# 1_ESP32-S3.net
KiCad netlist of a schematic drawn in Altium Designer
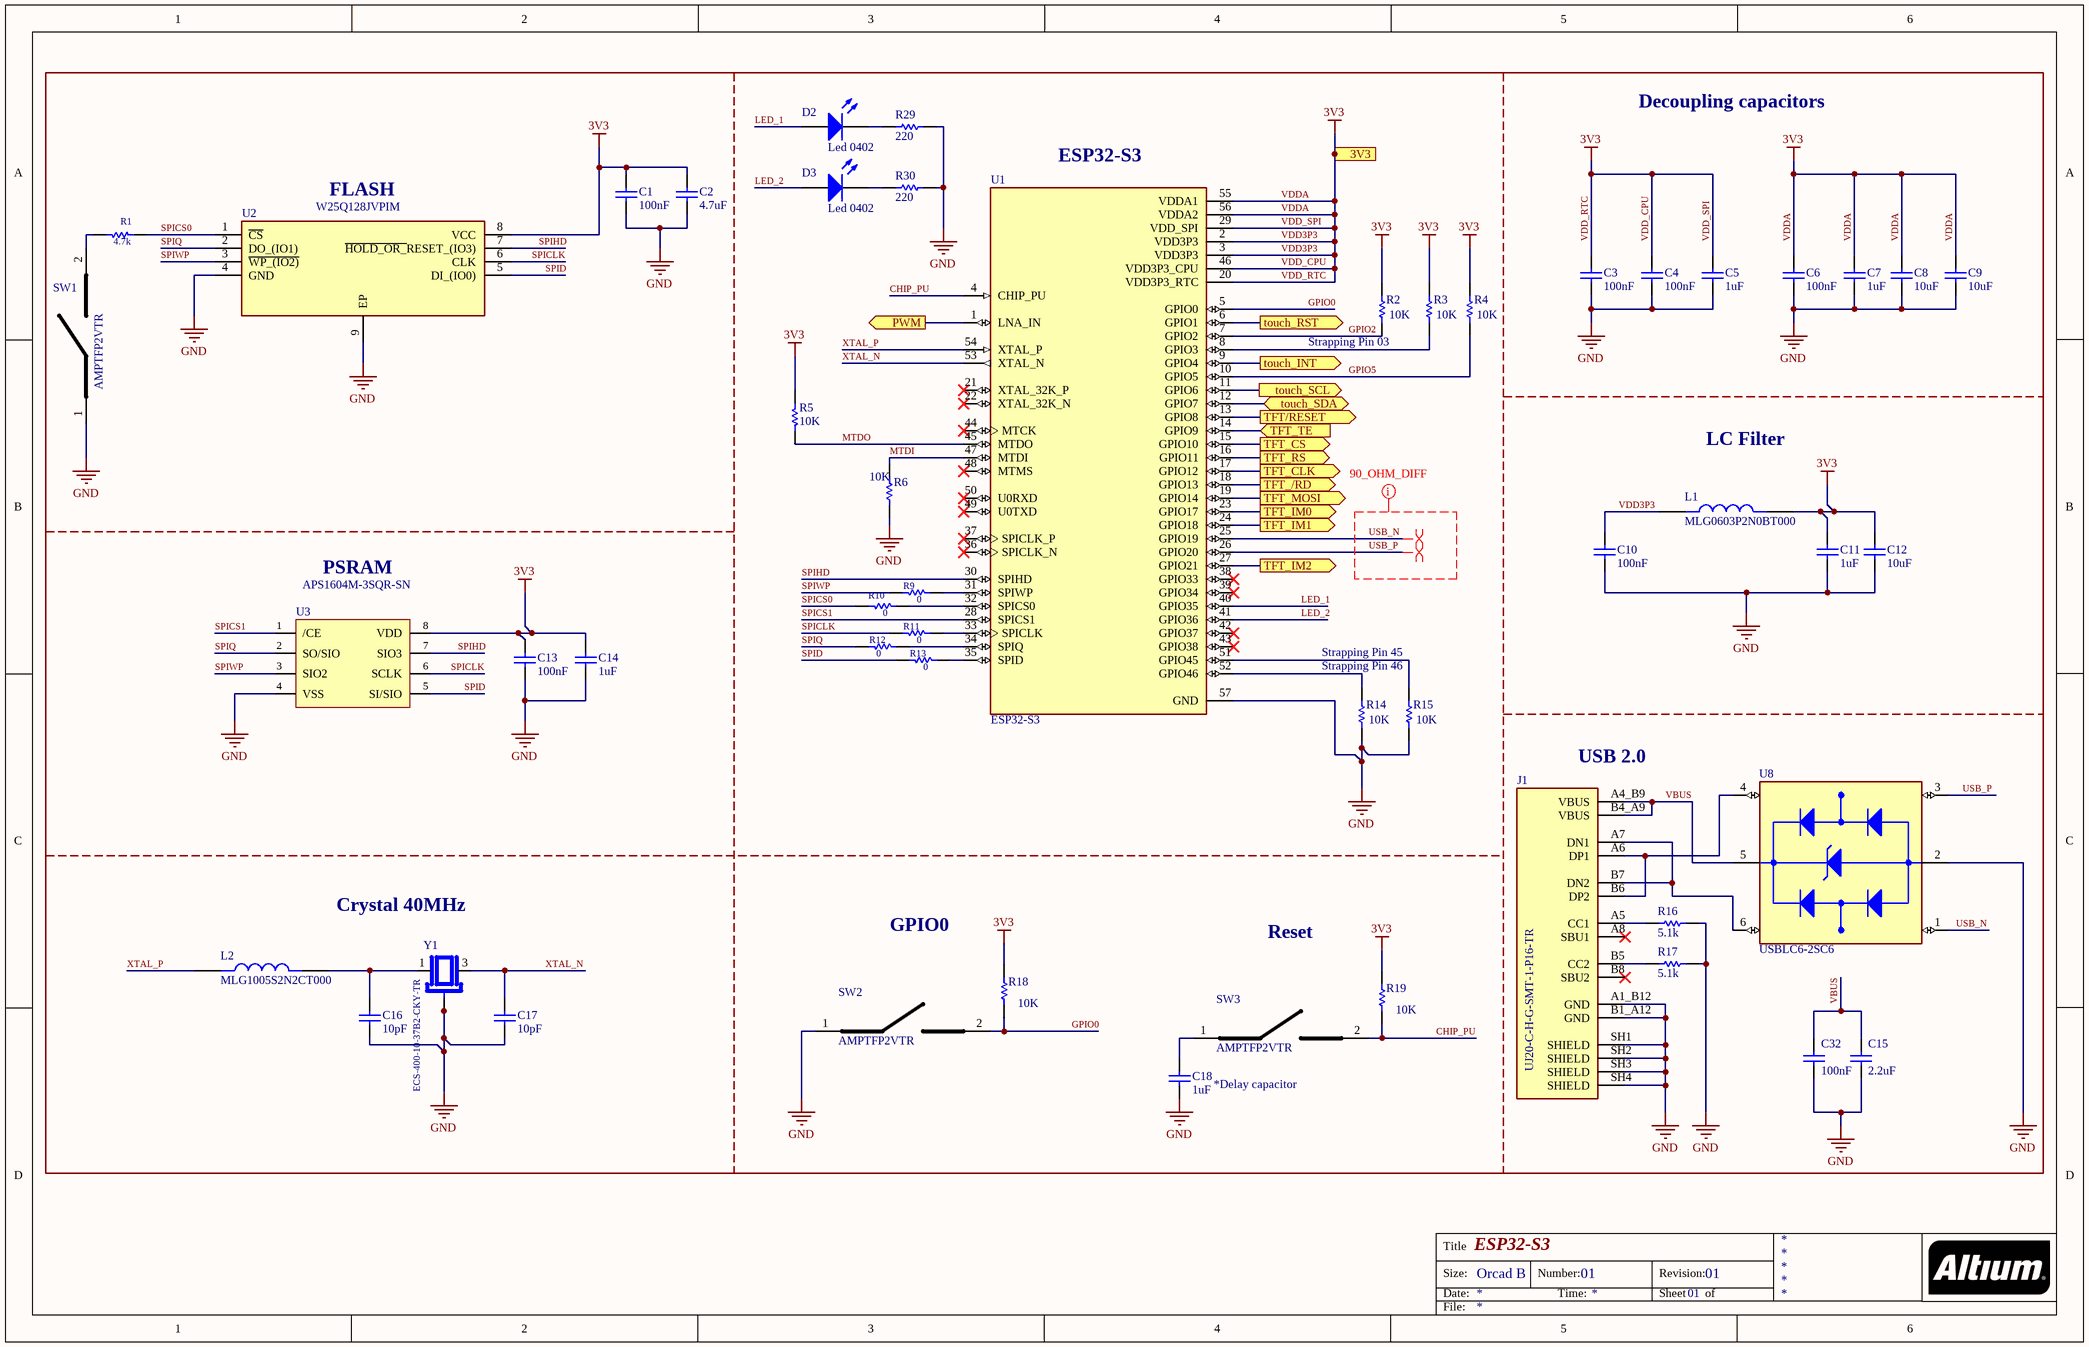
[diagram p0: [1] ESP32-S3.SchDoc]

(export (version "E")
  (design (tool "Eeschema 10.0.6"))
  (components
    (comp (ref "C1")
      (value "100nF")
      (footprint "Capacitor 0402")
      (description "Capacitor Ceramico SMD 0402")
      (libsource (lib "Mi Libreria") (part "Capacitor 0402"))
    )
    (comp (ref "C2")
      (value "4.7uF")
      (footprint "Capacitor 0402")
      (description "Capacitor Ceramico SMD 0402")
      (libsource (lib "Mi Libreria") (part "Capacitor 0402"))
    )
    (comp (ref "C3")
      (value "100nF")
      (footprint "Capacitor 0402")
      (description "Capacitor Ceramico SMD 0402")
      (libsource (lib "Mi Libreria") (part "Capacitor 0402"))
    )
    (comp (ref "C4")
      (value "100nF")
      (footprint "Capacitor 0402")
      (description "Capacitor Ceramico SMD 0402")
      (libsource (lib "Mi Libreria") (part "Capacitor 0402"))
    )
    (comp (ref "C5")
      (value "1uF")
      (footprint "Capacitor 0402")
      (description "Capacitor Ceramico SMD 0402")
      (libsource (lib "Mi Libreria") (part "Capacitor 0402"))
    )
    (comp (ref "C6")
      (value "100nF")
      (footprint "Capacitor 0402")
      (description "Capacitor Ceramico SMD 0402")
      (libsource (lib "Mi Libreria") (part "Capacitor 0402"))
    )
    (comp (ref "C7")
      (value "1uF")
      (footprint "Capacitor 0402")
      (description "Capacitor Ceramico SMD 0402")
      (libsource (lib "Mi Libreria") (part "Capacitor 0402"))
    )
    (comp (ref "C8")
      (value "10uF")
      (footprint "Capacitor 0603")
      (description "Capacitor Ceramico SMD 0603")
      (libsource (lib "Mi Libreria") (part "Capacitor 0603"))
    )
    (comp (ref "C9")
      (value "10uF")
      (footprint "Capacitor 0603")
      (description "Capacitor Ceramico SMD 0603")
      (libsource (lib "Mi Libreria") (part "Capacitor 0603"))
    )
    (comp (ref "C10")
      (value "100nF")
      (footprint "Capacitor 0402")
      (description "Capacitor Ceramico SMD 0402")
      (libsource (lib "Mi Libreria") (part "Capacitor 0402"))
    )
    (comp (ref "C11")
      (value "1uF")
      (footprint "Capacitor 0402")
      (description "Capacitor Ceramico SMD 0402")
      (libsource (lib "Mi Libreria") (part "Capacitor 0402"))
    )
    (comp (ref "C12")
      (value "10uF")
      (footprint "Capacitor 0603")
      (description "Capacitor Ceramico SMD 0603")
      (libsource (lib "Mi Libreria") (part "Capacitor 0603"))
    )
    (comp (ref "C13")
      (value "100nF")
      (footprint "Capacitor 0402")
      (description "Capacitor Ceramico SMD 0402")
      (libsource (lib "Mi Libreria") (part "Capacitor 0402"))
    )
    (comp (ref "C14")
      (value "1uF")
      (footprint "Capacitor 0402")
      (description "Capacitor Ceramico SMD 0402")
      (libsource (lib "Mi Libreria") (part "Capacitor 0402"))
    )
    (comp (ref "C15")
      (value "2.2uF")
      (footprint "Capacitor 0402")
      (description "Capacitor Ceramico SMD 0402")
      (libsource (lib "Mi Libreria") (part "Capacitor 0402"))
    )
    (comp (ref "C16")
      (value "10pF")
      (footprint "Capacitor 0402")
      (description "Capacitor Ceramico SMD 0402")
      (libsource (lib "Mi Libreria") (part "Capacitor 0402"))
    )
    (comp (ref "C17")
      (value "10pF")
      (footprint "Capacitor 0402")
      (description "Capacitor Ceramico SMD 0402")
      (libsource (lib "Mi Libreria") (part "Capacitor 0402"))
    )
    (comp (ref "C18")
      (value "1uF")
      (footprint "Capacitor 0402")
      (description "Capacitor Ceramico SMD 0402")
      (libsource (lib "Mi Libreria") (part "Capacitor 0402"))
    )
    (comp (ref "C32")
      (value "100nF")
      (footprint "Capacitor 0402")
      (description "Capacitor Ceramico SMD 0402")
      (libsource (lib "Mi Libreria") (part "Capacitor 0402"))
    )
    (comp (ref "D2")
      (value "Led 0402")
      (footprint "LED 0402")
      (description "LED SMD 0402")
      (libsource (lib "Led & Displays") (part "LED 0402"))
    )
    (comp (ref "D3")
      (value "Led 0402")
      (footprint "LED 0402")
      (description "LED SMD 0402")
      (libsource (lib "Led & Displays") (part "LED 0402"))
    )
    (comp (ref "J1")
      (value "UJ20-C-H-G-SMT-1-P16-TR")
      (footprint "SAMESKY_UJ20-C-H-G-SMT-1-P16-TR")
      (fields (field (name "MF") "Same Sky"))
      (libsource (lib "UJ20-C-H-G-SMT-1-P16-TR") (part "UJ20-C-H-G-SMT-1-P16-TR"))
    )
    (comp (ref "L1")
      (value "MLG0603P2N0BT000")
      (footprint "INDC0603X33N")
      (description "2 nH Unshielded Multilayer Inductor 600 mA 100mOhm Max 0201 (0603 Metric)")
      (fields (field (name "MF") "TDK"))
      (libsource (lib "MLG0603P2N0BT000") (part "MLG0603P2N0BT000"))
    )
    (comp (ref "L2")
      (value "MLG1005S2N2CT000")
      (footprint "INDC1005X55N")
      (description "FIXED IND 2.2NH 900MA 150MOHM SM")
      (fields (field (name "MF") "TDK Corporation"))
      (libsource (lib "0402inductor") (part "MLG1005S2N2CT000"))
    )
    (comp (ref "R1")
      (value "4.7k")
      (footprint "Resistencia 0402")
      (description "Resistencia SMD 0402")
      (libsource (lib "Mi Libreria") (part "Resistencia SMD 0402"))
    )
    (comp (ref "R2")
      (value "10K")
      (footprint "Resistencia 0402")
      (description "Resistencia SMD 0402")
      (libsource (lib "Mi Libreria") (part "Resistencia SMD 0402"))
    )
    (comp (ref "R3")
      (value "10K")
      (footprint "Resistencia 0402")
      (description "Resistencia SMD 0402")
      (libsource (lib "Mi Libreria") (part "Resistencia SMD 0402"))
    )
    (comp (ref "R4")
      (value "10K")
      (footprint "Resistencia 0402")
      (description "Resistencia SMD 0402")
      (libsource (lib "Mi Libreria") (part "Resistencia SMD 0402"))
    )
    (comp (ref "R5")
      (value "10K")
      (footprint "Resistencia 0402")
      (description "Resistencia SMD 0402")
      (libsource (lib "Mi Libreria") (part "Resistencia SMD 0402"))
    )
    (comp (ref "R6")
      (value "10K")
      (footprint "Resistencia 0402")
      (description "Resistencia SMD 0402")
      (libsource (lib "Mi Libreria") (part "Resistencia SMD 0402"))
    )
    (comp (ref "R9")
      (value "0")
      (footprint "Resistencia 0402")
      (description "Resistencia SMD 0402")
      (libsource (lib "Mi Libreria") (part "Resistencia SMD 0402"))
    )
    (comp (ref "R10")
      (value "0")
      (footprint "Resistencia 0402")
      (description "Resistencia SMD 0402")
      (libsource (lib "Mi Libreria") (part "Resistencia SMD 0402"))
    )
    (comp (ref "R11")
      (value "0")
      (footprint "Resistencia 0402")
      (description "Resistencia SMD 0402")
      (libsource (lib "Mi Libreria") (part "Resistencia SMD 0402"))
    )
    (comp (ref "R12")
      (value "0")
      (footprint "Resistencia 0402")
      (description "Resistencia SMD 0402")
      (libsource (lib "Mi Libreria") (part "Resistencia SMD 0402"))
    )
    (comp (ref "R13")
      (value "0")
      (footprint "Resistencia 0402")
      (description "Resistencia SMD 0402")
      (libsource (lib "Mi Libreria") (part "Resistencia SMD 0402"))
    )
    (comp (ref "R14")
      (value "10K")
      (footprint "Resistencia 0402")
      (description "Resistencia SMD 0402")
      (libsource (lib "Mi Libreria") (part "Resistencia SMD 0402"))
    )
    (comp (ref "R15")
      (value "10K")
      (footprint "Resistencia 0402")
      (description "Resistencia SMD 0402")
      (libsource (lib "Mi Libreria") (part "Resistencia SMD 0402"))
    )
    (comp (ref "R16")
      (value "5.1k")
      (footprint "Resistencia 0402")
      (description "Resistencia SMD 0402")
      (libsource (lib "Mi Libreria") (part "Resistencia SMD 0402"))
    )
    (comp (ref "R17")
      (value "5.1k")
      (footprint "Resistencia 0402")
      (description "Resistencia SMD 0402")
      (libsource (lib "Mi Libreria") (part "Resistencia SMD 0402"))
    )
    (comp (ref "R18")
      (value "10K")
      (footprint "Resistencia 0402")
      (description "Resistencia SMD 0402")
      (libsource (lib "Mi Libreria") (part "Resistencia SMD 0402"))
    )
    (comp (ref "R19")
      (value "10K")
      (footprint "Resistencia 0402")
      (description "Resistencia SMD 0402")
      (libsource (lib "Mi Libreria") (part "Resistencia SMD 0402"))
    )
    (comp (ref "R29")
      (value "220")
      (footprint "Resistencia 0402")
      (description "Resistencia SMD 0402")
      (libsource (lib "Mi Libreria") (part "Resistencia SMD 0402"))
    )
    (comp (ref "R30")
      (value "220")
      (footprint "Resistencia 0402")
      (description "Resistencia SMD 0402")
      (libsource (lib "Mi Libreria") (part "Resistencia SMD 0402"))
    )
    (comp (ref "SW1")
      (value "AMPTFP2VTR")
      (footprint "AMPTFP2VTR")
      (description "Tactile Switch SPST-NO Top Actuated Surface Mount")
      (fields (field (name "MOUSER PART NUMBER") "642-AMPTFP2VTR"))
      (libsource (lib "AMPTFP2VTR") (part "AMPTFP2VTR"))
    )
    (comp (ref "SW2")
      (value "AMPTFP2VTR")
      (footprint "AMPTFP2VTR")
      (description "Tactile Switch SPST-NO Top Actuated Surface Mount")
      (fields (field (name "MOUSER PART NUMBER") "642-AMPTFP2VTR"))
      (libsource (lib "AMPTFP2VTR") (part "AMPTFP2VTR"))
    )
    (comp (ref "SW3")
      (value "AMPTFP2VTR")
      (footprint "AMPTFP2VTR")
      (description "Tactile Switch SPST-NO Top Actuated Surface Mount")
      (fields (field (name "MOUSER PART NUMBER") "642-AMPTFP2VTR"))
      (libsource (lib "AMPTFP2VTR") (part "AMPTFP2VTR"))
    )
    (comp (ref "U1")
      (value "ESP32-S3")
      (footprint "IC_ESP32-S3")
      (fields (field (name "MF") "Espressif Systems"))
      (libsource (lib "ESP32-S3") (part "ESP32-S3"))
    )
    (comp (ref "U2")
      (value "W25Q128JVPIM")
      (footprint "SON127P600X500X80-9N-D")
      (description "128M-bit Serial Flash Memory with uniform 4KB sectors and Dual/Quad SPI")
      (fields (field (name "MOUSER PART NUMBER") "454-W25Q128JVPIM"))
      (libsource (lib "W25Q128JVPIM") (part "W25Q128JVPIM"))
    )
    (comp (ref "U3")
      (value "APS1604M-3SQR-SN")
      (footprint "SOIC127P600X165-8N")
      (description "DRAM IoT RAM 16Mb QSPI (x1,x4) SDR 133/84MHz, RBX, 3V, Ind. Temp., SOP8")
      (libsource (lib "APS1604M-3SQR-SN") (part "APS1604M-3SQR-SN"))
    )
    (comp (ref "U8")
      (value "USBLC6-2SC6")
      (footprint "SOT95P280X145-6N")
      (description "17V Clamp 5A (8/20Âµs) Ipp Tvs Diode Surface Mount SOT-23-6")
      (fields (field (name "MF") "STMicroelectronics"))
      (libsource (lib "USBLC6-2SC6") (part "USBLC6-2SC6"))
    )
    (comp (ref "Y1")
      (value "ECS-400-10-37B2-CKY-TR")
      (footprint "XTAL_ECS-400-10-37B2-CKY-TR")
      (libsource (lib "ECS-400-10-37B2-CKY-TR") (part "ECS-400-10-37B2-CKY-TR"))
    )
  )
  (nets
    (net (code "1") (name "/CHIP_PU") (class "Default")
      (node (ref "R19") (pin "1") (pinfunction "A_1") (pintype "passive"))
      (node (ref "SW3") (pin "2") (pinfunction "NO_2") (pintype "passive"))
      (node (ref "U1") (pin "4") (pinfunction "CHIP_PU_4") (pintype "input"))
    )
    (net (code "2") (name "/GPIO0") (class "Default")
      (node (ref "R18") (pin "1") (pinfunction "A_1") (pintype "passive"))
      (node (ref "SW2") (pin "2") (pinfunction "NO_2") (pintype "passive"))
      (node (ref "U1") (pin "5") (pinfunction "GPIO0_5") (pintype "bidirectional"))
    )
    (net (code "3") (name "/GPIO2") (class "Default")
      (node (ref "R2") (pin "1") (pinfunction "A_1") (pintype "passive"))
      (node (ref "U1") (pin "7") (pinfunction "GPIO2_7") (pintype "bidirectional"))
    )
    (net (code "4") (name "/GPIO5") (class "Default")
      (node (ref "R4") (pin "1") (pinfunction "A_1") (pintype "passive"))
      (node (ref "U1") (pin "10") (pinfunction "GPIO5_10") (pintype "bidirectional"))
    )
    (net (code "5") (name "/LED_1") (class "Default")
      (node (ref "D2") (pin "1") (pinfunction "A_1") (pintype "passive"))
      (node (ref "U1") (pin "40") (pinfunction "GPIO35_40") (pintype "bidirectional"))
    )
    (net (code "6") (name "/LED_2") (class "Default")
      (node (ref "D3") (pin "1") (pinfunction "A_1") (pintype "passive"))
      (node (ref "U1") (pin "41") (pinfunction "GPIO36_41") (pintype "bidirectional"))
    )
    (net (code "7") (name "/MTDI") (class "Default")
      (node (ref "R6") (pin "2") (pinfunction "B_2") (pintype "passive"))
      (node (ref "U1") (pin "47") (pinfunction "MTDI_47") (pintype "bidirectional"))
    )
    (net (code "8") (name "/MTDO") (class "Default")
      (node (ref "R5") (pin "1") (pinfunction "A_1") (pintype "passive"))
      (node (ref "U1") (pin "45") (pinfunction "MTDO_45") (pintype "bidirectional"))
    )
    (net (code "9") (name "/PWM") (class "Default")
      (node (ref "U1") (pin "1") (pinfunction "LNA_IN_1") (pintype "bidirectional"))
    )
    (net (code "10") (name "/SPICLK") (class "Default")
      (node (ref "R11") (pin "2") (pinfunction "B_2") (pintype "passive"))
      (node (ref "U2") (pin "6") (pinfunction "CLK_6") (pintype "passive"))
      (node (ref "U3") (pin "6") (pinfunction "SCLK_6") (pintype "passive"))
    )
    (net (code "11") (name "/SPICS0") (class "Default")
      (node (ref "R1") (pin "1") (pinfunction "A_1") (pintype "passive"))
      (node (ref "R10") (pin "1") (pinfunction "A_1") (pintype "passive"))
      (node (ref "U2") (pin "1") (pinfunction "~{CS}_1") (pintype "passive"))
    )
    (net (code "12") (name "/SPICS1") (class "Default")
      (node (ref "U1") (pin "28") (pinfunction "SPICS1_28") (pintype "bidirectional"))
      (node (ref "U3") (pin "1") (pinfunction "/CE_1") (pintype "passive"))
    )
    (net (code "13") (name "/SPID") (class "Default")
      (node (ref "R13") (pin "2") (pinfunction "B_2") (pintype "passive"))
      (node (ref "U2") (pin "5") (pinfunction "DI_(IO0)_5") (pintype "passive"))
      (node (ref "U3") (pin "5") (pinfunction "SI/SIO_5") (pintype "passive"))
    )
    (net (code "14") (name "/SPIHD") (class "Default")
      (node (ref "U1") (pin "30") (pinfunction "SPIHD_30") (pintype "bidirectional"))
      (node (ref "U2") (pin "7") (pinfunction "~{HOLD_OR_}RESET_(IO3)_7") (pintype "passive"))
      (node (ref "U3") (pin "7") (pinfunction "SIO3_7") (pintype "passive"))
    )
    (net (code "15") (name "/SPIQ") (class "Default")
      (node (ref "R12") (pin "2") (pinfunction "B_2") (pintype "passive"))
      (node (ref "U2") (pin "2") (pinfunction "DO_(IO1)_2") (pintype "passive"))
      (node (ref "U3") (pin "2") (pinfunction "SO/SIO_2") (pintype "passive"))
    )
    (net (code "16") (name "/SPIWP") (class "Default")
      (node (ref "R9") (pin "2") (pinfunction "B_2") (pintype "passive"))
      (node (ref "U2") (pin "3") (pinfunction "~{WP_(IO2)}_3") (pintype "passive"))
      (node (ref "U3") (pin "3") (pinfunction "SIO2_3") (pintype "passive"))
    )
    (net (code "17") (name "/TFT_CLK") (class "Default")
      (node (ref "U1") (pin "17") (pinfunction "GPIO12_17") (pintype "bidirectional"))
    )
    (net (code "18") (name "/TFT_CS") (class "Default")
      (node (ref "U1") (pin "15") (pinfunction "GPIO10_15") (pintype "bidirectional"))
    )
    (net (code "19") (name "/TFT_IM0") (class "Default")
      (node (ref "U1") (pin "23") (pinfunction "GPIO17_23") (pintype "bidirectional"))
    )
    (net (code "20") (name "/TFT_IM1") (class "Default")
      (node (ref "U1") (pin "24") (pinfunction "GPIO18_24") (pintype "bidirectional"))
    )
    (net (code "21") (name "/TFT_IM2") (class "Default")
      (node (ref "U1") (pin "27") (pinfunction "GPIO21_27") (pintype "bidirectional"))
    )
    (net (code "22") (name "/TFT_MOSI") (class "Default")
      (node (ref "U1") (pin "19") (pinfunction "GPIO14_19") (pintype "bidirectional"))
    )
    (net (code "23") (name "/TFT_RS") (class "Default")
      (node (ref "U1") (pin "16") (pinfunction "GPIO11_16") (pintype "bidirectional"))
    )
    (net (code "24") (name "/TFT_TE") (class "Default")
      (node (ref "U1") (pin "14") (pinfunction "GPIO9_14") (pintype "bidirectional"))
    )
    (net (code "25") (name "/TFT_{slash}RD") (class "Default")
      (node (ref "U1") (pin "18") (pinfunction "GPIO13_18") (pintype "bidirectional"))
    )
    (net (code "26") (name "/TFT{slash}RESET") (class "Default")
      (node (ref "U1") (pin "13") (pinfunction "GPIO8_13") (pintype "bidirectional"))
    )
    (net (code "27") (name "/USB_N") (class "Default")
      (node (ref "U1") (pin "25") (pinfunction "GPIO19_25") (pintype "bidirectional"))
      (node (ref "U8") (pin "1") (pinfunction "I/O1_IN_1") (pintype "bidirectional"))
    )
    (net (code "28") (name "/USB_P") (class "Default")
      (node (ref "U1") (pin "26") (pinfunction "GPIO20_26") (pintype "bidirectional"))
      (node (ref "U8") (pin "3") (pinfunction "I/O2_IN_3") (pintype "bidirectional"))
    )
    (net (code "29") (name "/VBUS") (class "Default")
      (node (ref "C15") (pin "2") (pinfunction "2_2") (pintype "passive"))
      (node (ref "C32") (pin "2") (pinfunction "2_2") (pintype "passive"))
      (node (ref "J1") (pin "A4_B9") (pinfunction "VBUS_A4_B9") (pintype "passive"))
      (node (ref "J1") (pin "B4_A9") (pinfunction "VBUS_B4_A9") (pintype "passive"))
      (node (ref "U8") (pin "5") (pinfunction "VBUS_5") (pintype "power_in"))
    )
    (net (code "30") (name "/XTAL_N") (class "Default")
      (node (ref "C17") (pin "2") (pinfunction "2_2") (pintype "passive"))
      (node (ref "U1") (pin "53") (pinfunction "XTAL_N_53") (pintype "output"))
      (node (ref "Y1") (pin "3") (pinfunction "OUT/IN_3") (pintype "passive"))
    )
    (net (code "31") (name "/XTAL_P") (class "Default")
      (node (ref "L2") (pin "1") (pinfunction "1_1") (pintype "passive"))
      (node (ref "U1") (pin "54") (pinfunction "XTAL_P_54") (pintype "input"))
    )
    (net (code "32") (name "/touch_INT") (class "Default")
      (node (ref "U1") (pin "9") (pinfunction "GPIO4_9") (pintype "bidirectional"))
    )
    (net (code "33") (name "/touch_RST") (class "Default")
      (node (ref "U1") (pin "6") (pinfunction "GPIO1_6") (pintype "bidirectional"))
    )
    (net (code "34") (name "/touch_SCL") (class "Default")
      (node (ref "U1") (pin "11") (pinfunction "GPIO6_11") (pintype "bidirectional"))
    )
    (net (code "35") (name "/touch_SDA") (class "Default")
      (node (ref "U1") (pin "12") (pinfunction "GPIO7_12") (pintype "bidirectional"))
    )
    (net (code "36") (name "3V3") (class "Default")
      (node (ref "C1") (pin "2") (pinfunction "2_2") (pintype "passive"))
      (node (ref "C10") (pin "2") (pinfunction "2_2") (pintype "passive"))
      (node (ref "C11") (pin "2") (pinfunction "2_2") (pintype "passive"))
      (node (ref "C12") (pin "2") (pinfunction "2_2") (pintype "passive"))
      (node (ref "C13") (pin "2") (pinfunction "2_2") (pintype "passive"))
      (node (ref "C14") (pin "2") (pinfunction "2_2") (pintype "passive"))
      (node (ref "C2") (pin "2") (pinfunction "2_2") (pintype "passive"))
      (node (ref "C3") (pin "2") (pinfunction "2_2") (pintype "passive"))
      (node (ref "C4") (pin "2") (pinfunction "2_2") (pintype "passive"))
      (node (ref "C5") (pin "2") (pinfunction "2_2") (pintype "passive"))
      (node (ref "C6") (pin "2") (pinfunction "2_2") (pintype "passive"))
      (node (ref "C7") (pin "2") (pinfunction "2_2") (pintype "passive"))
      (node (ref "C8") (pin "2") (pinfunction "2_2") (pintype "passive"))
      (node (ref "C9") (pin "2") (pinfunction "2_2") (pintype "passive"))
      (node (ref "L1") (pin "1") (pinfunction "1_1") (pintype "passive"))
      (node (ref "L1") (pin "2") (pinfunction "2_2") (pintype "passive"))
      (node (ref "R18") (pin "2") (pinfunction "B_2") (pintype "passive"))
      (node (ref "R19") (pin "2") (pinfunction "B_2") (pintype "passive"))
      (node (ref "R2") (pin "2") (pinfunction "B_2") (pintype "passive"))
      (node (ref "R3") (pin "2") (pinfunction "B_2") (pintype "passive"))
      (node (ref "R4") (pin "2") (pinfunction "B_2") (pintype "passive"))
      (node (ref "R5") (pin "2") (pinfunction "B_2") (pintype "passive"))
      (node (ref "U1") (pin "2") (pinfunction "VDD3P3_2") (pintype "power_in"))
      (node (ref "U1") (pin "20") (pinfunction "VDD3P3_RTC_20") (pintype "power_in"))
      (node (ref "U1") (pin "29") (pinfunction "VDD_SPI_29") (pintype "power_in"))
      (node (ref "U1") (pin "3") (pinfunction "VDD3P3_3") (pintype "power_in"))
      (node (ref "U1") (pin "46") (pinfunction "VDD3P3_CPU_46") (pintype "power_in"))
      (node (ref "U1") (pin "55") (pinfunction "VDDA1_55") (pintype "power_in"))
      (node (ref "U1") (pin "56") (pinfunction "VDDA2_56") (pintype "power_in"))
      (node (ref "U2") (pin "8") (pinfunction "VCC_8") (pintype "passive"))
      (node (ref "U3") (pin "8") (pinfunction "VDD_8") (pintype "passive"))
    )
    (net (code "37") (name "GND") (class "Default")
      (node (ref "C1") (pin "1") (pinfunction "1_1") (pintype "passive"))
      (node (ref "C10") (pin "1") (pinfunction "1_1") (pintype "passive"))
      (node (ref "C11") (pin "1") (pinfunction "1_1") (pintype "passive"))
      (node (ref "C12") (pin "1") (pinfunction "1_1") (pintype "passive"))
      (node (ref "C13") (pin "1") (pinfunction "1_1") (pintype "passive"))
      (node (ref "C14") (pin "1") (pinfunction "1_1") (pintype "passive"))
      (node (ref "C15") (pin "1") (pinfunction "1_1") (pintype "passive"))
      (node (ref "C16") (pin "1") (pinfunction "1_1") (pintype "passive"))
      (node (ref "C17") (pin "1") (pinfunction "1_1") (pintype "passive"))
      (node (ref "C18") (pin "1") (pinfunction "1_1") (pintype "passive"))
      (node (ref "C2") (pin "1") (pinfunction "1_1") (pintype "passive"))
      (node (ref "C3") (pin "1") (pinfunction "1_1") (pintype "passive"))
      (node (ref "C32") (pin "1") (pinfunction "1_1") (pintype "passive"))
      (node (ref "C4") (pin "1") (pinfunction "1_1") (pintype "passive"))
      (node (ref "C5") (pin "1") (pinfunction "1_1") (pintype "passive"))
      (node (ref "C6") (pin "1") (pinfunction "1_1") (pintype "passive"))
      (node (ref "C7") (pin "1") (pinfunction "1_1") (pintype "passive"))
      (node (ref "C8") (pin "1") (pinfunction "1_1") (pintype "passive"))
      (node (ref "C9") (pin "1") (pinfunction "1_1") (pintype "passive"))
      (node (ref "J1") (pin "A1_B12") (pinfunction "GND_A1_B12") (pintype "passive"))
      (node (ref "J1") (pin "B1_A12") (pinfunction "GND_B1_A12") (pintype "passive"))
      (node (ref "J1") (pin "SH1") (pinfunction "SHIELD_SH1") (pintype "passive"))
      (node (ref "J1") (pin "SH2") (pinfunction "SHIELD_SH2") (pintype "passive"))
      (node (ref "J1") (pin "SH3") (pinfunction "SHIELD_SH3") (pintype "passive"))
      (node (ref "J1") (pin "SH4") (pinfunction "SHIELD_SH4") (pintype "passive"))
      (node (ref "R14") (pin "1") (pinfunction "A_1") (pintype "passive"))
      (node (ref "R15") (pin "1") (pinfunction "A_1") (pintype "passive"))
      (node (ref "R16") (pin "1") (pinfunction "A_1") (pintype "passive"))
      (node (ref "R17") (pin "1") (pinfunction "A_1") (pintype "passive"))
      (node (ref "R29") (pin "2") (pinfunction "B_2") (pintype "passive"))
      (node (ref "R30") (pin "2") (pinfunction "B_2") (pintype "passive"))
      (node (ref "R6") (pin "1") (pinfunction "A_1") (pintype "passive"))
      (node (ref "SW1") (pin "1") (pinfunction "COM_1") (pintype "passive"))
      (node (ref "SW2") (pin "1") (pinfunction "COM_1") (pintype "passive"))
      (node (ref "U1") (pin "57") (pinfunction "GND_57") (pintype "power_in"))
      (node (ref "U2") (pin "4") (pinfunction "GND_4") (pintype "passive"))
      (node (ref "U2") (pin "9") (pinfunction "EP_9") (pintype "passive"))
      (node (ref "U3") (pin "4") (pinfunction "VSS_4") (pintype "passive"))
      (node (ref "U8") (pin "2") (pinfunction "GND_2") (pintype "power_in"))
      (node (ref "Y1") (pin "2") (pinfunction "GND_2") (pintype "power_in"))
      (node (ref "Y1") (pin "4") (pinfunction "GND_4") (pintype "power_in"))
    )
    (net (code "38") (name "Net-(D2-K)") (class "Default")
      (node (ref "D2") (pin "2") (pinfunction "K_2") (pintype "passive"))
      (node (ref "R29") (pin "1") (pinfunction "A_1") (pintype "passive"))
    )
    (net (code "39") (name "Net-(D3-K)") (class "Default")
      (node (ref "D3") (pin "2") (pinfunction "K_2") (pintype "passive"))
      (node (ref "R30") (pin "1") (pinfunction "A_1") (pintype "passive"))
    )
    (net (code "40") (name "Net-(J1-CC1)") (class "Default")
      (node (ref "J1") (pin "A5") (pinfunction "CC1_A5") (pintype "passive"))
      (node (ref "R16") (pin "2") (pinfunction "B_2") (pintype "passive"))
    )
    (net (code "41") (name "Net-(J1-CC2)") (class "Default")
      (node (ref "J1") (pin "B5") (pinfunction "CC2_B5") (pintype "passive"))
      (node (ref "R17") (pin "2") (pinfunction "B_2") (pintype "passive"))
    )
    (net (code "42") (name "Net-(J1-DN1)") (class "Default")
      (node (ref "J1") (pin "A7") (pinfunction "DN1_A7") (pintype "passive"))
      (node (ref "J1") (pin "B7") (pinfunction "DN2_B7") (pintype "passive"))
      (node (ref "U8") (pin "6") (pinfunction "I/O1_OUT_6") (pintype "bidirectional"))
    )
    (net (code "43") (name "Net-(J1-DP1)") (class "Default")
      (node (ref "J1") (pin "A6") (pinfunction "DP1_A6") (pintype "passive"))
      (node (ref "J1") (pin "B6") (pinfunction "DP2_B6") (pintype "passive"))
      (node (ref "U8") (pin "4") (pinfunction "I/O2_OUT_4") (pintype "bidirectional"))
    )
    (net (code "44") (name "Net-(R1-B)") (class "Default")
      (node (ref "R1") (pin "2") (pinfunction "B_2") (pintype "passive"))
      (node (ref "SW1") (pin "2") (pinfunction "NO_2") (pintype "passive"))
    )
    (net (code "45") (name "Net-(R3-A)") (class "Default")
      (node (ref "R3") (pin "1") (pinfunction "A_1") (pintype "passive"))
      (node (ref "U1") (pin "8") (pinfunction "GPIO3_8") (pintype "bidirectional"))
    )
    (net (code "46") (name "Net-(R9-A)") (class "Default")
      (node (ref "R9") (pin "1") (pinfunction "A_1") (pintype "passive"))
      (node (ref "U1") (pin "31") (pinfunction "SPIWP_31") (pintype "bidirectional"))
    )
    (net (code "47") (name "Net-(R10-B)") (class "Default")
      (node (ref "R10") (pin "2") (pinfunction "B_2") (pintype "passive"))
      (node (ref "U1") (pin "32") (pinfunction "SPICS0_32") (pintype "bidirectional"))
    )
    (net (code "48") (name "Net-(R11-A)") (class "Default")
      (node (ref "R11") (pin "1") (pinfunction "A_1") (pintype "passive"))
      (node (ref "U1") (pin "33") (pinfunction "SPICLK_33") (pintype "bidirectional"))
    )
    (net (code "49") (name "Net-(R12-A)") (class "Default")
      (node (ref "R12") (pin "1") (pinfunction "A_1") (pintype "passive"))
      (node (ref "U1") (pin "34") (pinfunction "SPIQ_34") (pintype "bidirectional"))
    )
    (net (code "50") (name "Net-(R13-A)") (class "Default")
      (node (ref "R13") (pin "1") (pinfunction "A_1") (pintype "passive"))
      (node (ref "U1") (pin "35") (pinfunction "SPID_35") (pintype "bidirectional"))
    )
    (net (code "51") (name "Net-(R14-B)") (class "Default")
      (node (ref "R14") (pin "2") (pinfunction "B_2") (pintype "passive"))
      (node (ref "U1") (pin "52") (pinfunction "GPIO46_52") (pintype "bidirectional"))
    )
    (net (code "52") (name "Net-(R15-B)") (class "Default")
      (node (ref "R15") (pin "2") (pinfunction "B_2") (pintype "passive"))
      (node (ref "U1") (pin "51") (pinfunction "GPIO45_51") (pintype "bidirectional"))
    )
    (net (code "53") (name "Net-(SW3-COM)") (class "Default")
      (node (ref "C18") (pin "2") (pinfunction "2_2") (pintype "passive"))
      (node (ref "SW3") (pin "1") (pinfunction "COM_1") (pintype "passive"))
    )
    (net (code "54") (name "Net-(Y1-IN{slash}OUT)") (class "Default")
      (node (ref "C16") (pin "2") (pinfunction "2_2") (pintype "passive"))
      (node (ref "L2") (pin "2") (pinfunction "2_2") (pintype "passive"))
      (node (ref "Y1") (pin "1") (pinfunction "IN/OUT_1") (pintype "passive"))
    )
    (net (code "55") (name "unconnected-(J1-SBU1-PadA8)") (class "Default")
      (node (ref "J1") (pin "A8") (pinfunction "SBU1_A8") (pintype "passive+no_connect"))
    )
    (net (code "56") (name "unconnected-(J1-SBU2-PadB8)") (class "Default")
      (node (ref "J1") (pin "B8") (pinfunction "SBU2_B8") (pintype "passive+no_connect"))
    )
    (net (code "57") (name "unconnected-(U1-GPIO33-Pad38)") (class "Default")
      (node (ref "U1") (pin "38") (pinfunction "GPIO33_38") (pintype "bidirectional+no_connect"))
    )
    (net (code "58") (name "unconnected-(U1-GPIO34-Pad39)") (class "Default")
      (node (ref "U1") (pin "39") (pinfunction "GPIO34_39") (pintype "bidirectional+no_connect"))
    )
    (net (code "59") (name "unconnected-(U1-GPIO37-Pad42)") (class "Default")
      (node (ref "U1") (pin "42") (pinfunction "GPIO37_42") (pintype "bidirectional+no_connect"))
    )
    (net (code "60") (name "unconnected-(U1-GPIO38-Pad43)") (class "Default")
      (node (ref "U1") (pin "43") (pinfunction "GPIO38_43") (pintype "bidirectional+no_connect"))
    )
    (net (code "61") (name "unconnected-(U1-MTCK-Pad44)") (class "Default")
      (node (ref "U1") (pin "44") (pinfunction "MTCK_44") (pintype "bidirectional+no_connect"))
    )
    (net (code "62") (name "unconnected-(U1-MTMS-Pad48)") (class "Default")
      (node (ref "U1") (pin "48") (pinfunction "MTMS_48") (pintype "bidirectional+no_connect"))
    )
    (net (code "63") (name "unconnected-(U1-SPICLK_N-Pad36)") (class "Default")
      (node (ref "U1") (pin "36") (pinfunction "SPICLK_N_36") (pintype "bidirectional+no_connect"))
    )
    (net (code "64") (name "unconnected-(U1-SPICLK_P-Pad37)") (class "Default")
      (node (ref "U1") (pin "37") (pinfunction "SPICLK_P_37") (pintype "bidirectional+no_connect"))
    )
    (net (code "65") (name "unconnected-(U1-U0RXD-Pad50)") (class "Default")
      (node (ref "U1") (pin "50") (pinfunction "U0RXD_50") (pintype "bidirectional+no_connect"))
    )
    (net (code "66") (name "unconnected-(U1-U0TXD-Pad49)") (class "Default")
      (node (ref "U1") (pin "49") (pinfunction "U0TXD_49") (pintype "bidirectional+no_connect"))
    )
    (net (code "67") (name "unconnected-(U1-XTAL_32K_N-Pad22)") (class "Default")
      (node (ref "U1") (pin "22") (pinfunction "XTAL_32K_N_22") (pintype "bidirectional+no_connect"))
    )
    (net (code "68") (name "unconnected-(U1-XTAL_32K_P-Pad21)") (class "Default")
      (node (ref "U1") (pin "21") (pinfunction "XTAL_32K_P_21") (pintype "bidirectional+no_connect"))
    )
  )
)
